# Module4_1.net
KiCad netlist of a schematic drawn in EAGLE
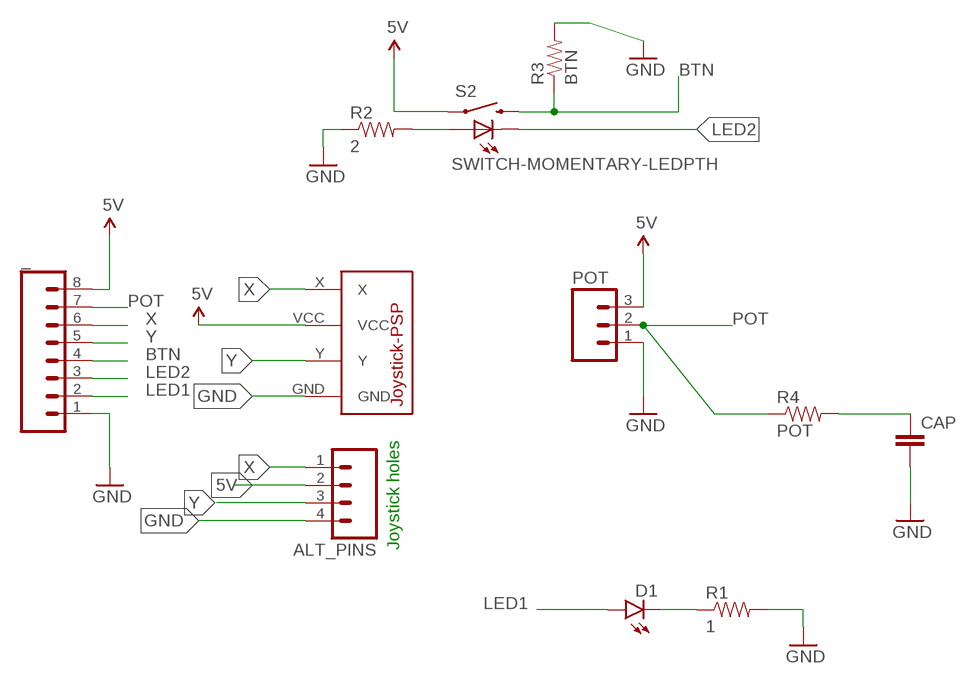
[diagram p0: schematic, sheet 1]

(export (version "E")
  (design (tool "Eeschema 10.0.6"))
  (components
    (comp (ref "ALT_PINS")
      (value "M04NO_SILK_ALL_ROUND")
      (footprint "eagle-import:1X04_NO_SILK_ALL_ROUND")
      (libsource (lib "eagle-import") (part "M04NO_SILK_ALL_ROUND"))
    )
    (comp (ref "CAP")
      (value "CAPEZ")
      (footprint "eagle-import:CAP-PTH-SMALLEZ")
      (libsource (lib "eagle-import") (part "CAPEZ"))
    )
    (comp (ref "D1")
      (value "LED3MM")
      (footprint "eagle-import:LED3MM")
      (libsource (lib "eagle-import") (part "LED3MM"))
    )
    (comp (ref "POT")
      (value "M031X03_NO_SILK")
      (footprint "eagle-import:1X03_NO_SILK")
      (libsource (lib "eagle-import") (part "M031X03_NO_SILK"))
    )
    (comp (ref "R1")
      (value "1")
      (footprint "eagle-import:AXIAL-0.3-KIT")
      (libsource (lib "eagle-import") (part "10KOHM-1/6W-5%(PTH)KIT"))
    )
    (comp (ref "R2")
      (value "2")
      (footprint "eagle-import:AXIAL-0.3-KIT")
      (libsource (lib "eagle-import") (part "10KOHM-1/6W-5%(PTH)KIT"))
    )
    (comp (ref "R3")
      (value "BTN")
      (footprint "eagle-import:AXIAL-0.3-KIT")
      (libsource (lib "eagle-import") (part "10KOHM-1/6W-5%(PTH)KIT"))
    )
    (comp (ref "R4")
      (value "POT")
      (footprint "eagle-import:AXIAL-0.3-KIT")
      (libsource (lib "eagle-import") (part "10KOHM-1/6W-5%(PTH)KIT"))
    )
    (comp (ref "S2")
      (value "SWITCH-MOMENTARY-LEDPTH")
      (footprint "eagle-import:TACTILE-PTH-LED-12MM")
      (libsource (lib "eagle-import") (part "SWITCH-MOMENTARY-LEDPTH"))
    )
    (comp (ref "U$1")
      (value "JOYSTICK-PSP1000")
      (footprint "eagle-import:JOYSTICK-PSP1000")
      (libsource (lib "eagle-import") (part "JOYSTICK-PSP1000"))
    )
    (comp (ref "_")
      (value "M08")
      (footprint "eagle-import:1X08_ROUND")
      (libsource (lib "eagle-import") (part "M08"))
    )
  )
  (nets
    (net (code "1") (name "/BTN") (class "Default")
      (node (ref "R3") (pin "P$1") (pinfunction "1_P$1") (pintype "passive"))
      (node (ref "S2") (pin "2") (pinfunction "2_2") (pintype "passive"))
      (node (ref "_") (pin "4") (pinfunction "4_4") (pintype "passive"))
    )
    (net (code "2") (name "/LED1") (class "Default")
      (node (ref "D1") (pin "A") (pinfunction "A_A") (pintype "passive"))
      (node (ref "_") (pin "2") (pinfunction "2_2") (pintype "passive"))
    )
    (net (code "3") (name "/POT") (class "Default")
      (node (ref "POT") (pin "2") (pinfunction "2_2") (pintype "passive"))
      (node (ref "R4") (pin "P$1") (pinfunction "1_P$1") (pintype "passive"))
      (node (ref "_") (pin "7") (pinfunction "7_7") (pintype "passive"))
    )
    (net (code "4") (name "5V") (class "Default")
      (node (ref "ALT_PINS") (pin "2") (pinfunction "2_2") (pintype "passive"))
      (node (ref "POT") (pin "3") (pinfunction "3_3") (pintype "passive"))
      (node (ref "S2") (pin "4") (pinfunction "1_4") (pintype "passive"))
      (node (ref "U$1") (pin "VCC") (pinfunction "VCC_VCC") (pintype "bidirectional"))
      (node (ref "_") (pin "8") (pinfunction "8_8") (pintype "passive"))
    )
    (net (code "5") (name "GND") (class "Default")
      (node (ref "ALT_PINS") (pin "4") (pinfunction "4_4") (pintype "passive"))
      (node (ref "CAP") (pin "2") (pinfunction "2_2") (pintype "passive"))
      (node (ref "POT") (pin "1") (pinfunction "1_1") (pintype "passive"))
      (node (ref "R1") (pin "P$2") (pinfunction "2_P$2") (pintype "passive"))
      (node (ref "R2") (pin "P$1") (pinfunction "1_P$1") (pintype "passive"))
      (node (ref "R3") (pin "P$2") (pinfunction "2_P$2") (pintype "passive"))
      (node (ref "U$1") (pin "GND") (pinfunction "GND_GND") (pintype "bidirectional"))
      (node (ref "_") (pin "1") (pinfunction "1_1") (pintype "passive"))
    )
    (net (code "6") (name "LED2") (class "Default")
      (node (ref "S2") (pin "C") (pinfunction "C_C") (pintype "passive"))
      (node (ref "_") (pin "3") (pinfunction "3_3") (pintype "passive"))
    )
    (net (code "7") (name "Net-(D1-C)") (class "Default")
      (node (ref "D1") (pin "K") (pinfunction "C_K") (pintype "passive"))
      (node (ref "R1") (pin "P$1") (pinfunction "1_P$1") (pintype "passive"))
    )
    (net (code "8") (name "Net-(R2-2)") (class "Default")
      (node (ref "R2") (pin "P$2") (pinfunction "2_P$2") (pintype "passive"))
      (node (ref "S2") (pin "A") (pinfunction "A_A") (pintype "passive"))
    )
    (net (code "9") (name "Net-(R4-2)") (class "Default")
      (node (ref "CAP") (pin "1") (pinfunction "1_1") (pintype "passive"))
      (node (ref "R4") (pin "P$2") (pinfunction "2_P$2") (pintype "passive"))
    )
    (net (code "10") (name "X") (class "Default")
      (node (ref "ALT_PINS") (pin "1") (pinfunction "1_1") (pintype "passive"))
      (node (ref "U$1") (pin "X") (pinfunction "X_X") (pintype "bidirectional"))
      (node (ref "_") (pin "6") (pinfunction "6_6") (pintype "passive"))
    )
    (net (code "11") (name "Y") (class "Default")
      (node (ref "ALT_PINS") (pin "3") (pinfunction "3_3") (pintype "passive"))
      (node (ref "U$1") (pin "Y") (pinfunction "Y_Y") (pintype "bidirectional"))
      (node (ref "_") (pin "5") (pinfunction "5_5") (pintype "passive"))
    )
  )
)
